# HolderDog_Simetric.net
KiCad netlist of a schematic drawn in Altium Designer
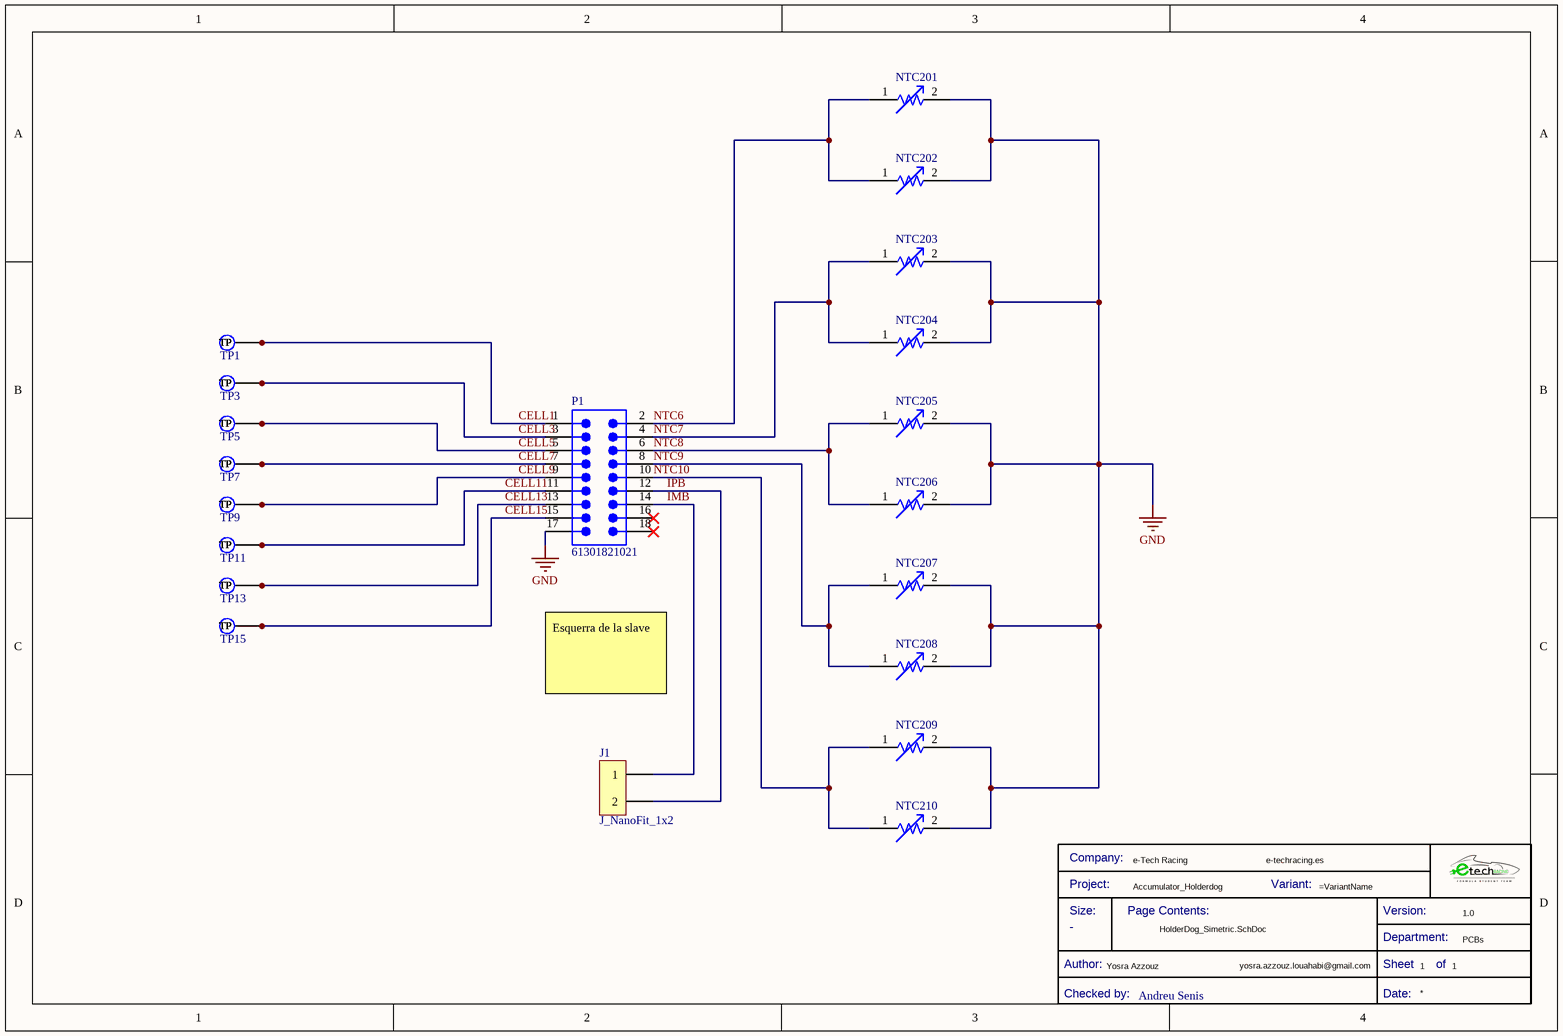
[diagram p0: HolderDog_Simetric.SchDoc]

(export (version "E")
  (design (tool "Eeschema 10.0.6"))
  (components
    (comp (ref "*")
      (value "Title Block_template")
      (description "Standard Title Block")
      (fields
        (field (name "SIZE") "-")
        (field (name ".CREATOR") "GP")
        (field (name ".PCBCHECK") "GP")
        (field (name ".SCHCHECK") "GP")
      )
      (libsource (lib "e-Tech_Racing") (part "Title Block_template"))
    )
    (comp (ref "J1")
      (value "J_NanoFit_1x2")
      (footprint "FP-105309-1102-MFG")
      (description "Conn HDR 2 POS 2.5mm Solder ST Thru-Hole 2 Terminal 1 Port Nano-Fit Tray")
      (libsource (lib "EMEA- E-Tech Racing- I'Escola d'Enginyeria de Barcelona Est") (part "Molex Nano-Fit"))
    )
    (comp (ref "NTC201")
      (value "NTC SMD 0805")
      (footprint "RESC2012X10N")
      (description "NTC 0805 package 10kR")
      (libsource (lib "EMEA- E-Tech Racing- I'Escola d'Enginyeria de Barcelona Est") (part "0805"))
    )
    (comp (ref "NTC202")
      (value "NTC SMD 0805")
      (footprint "RESC2012X10N")
      (description "NTC 0805 package 10kR")
      (libsource (lib "EMEA- E-Tech Racing- I'Escola d'Enginyeria de Barcelona Est") (part "0805"))
    )
    (comp (ref "NTC203")
      (value "NTC SMD 0805")
      (footprint "RESC2012X10N")
      (description "NTC 0805 package 10kR")
      (libsource (lib "EMEA- E-Tech Racing- I'Escola d'Enginyeria de Barcelona Est") (part "0805"))
    )
    (comp (ref "NTC204")
      (value "NTC SMD 0805")
      (footprint "RESC2012X10N")
      (description "NTC 0805 package 10kR")
      (libsource (lib "EMEA- E-Tech Racing- I'Escola d'Enginyeria de Barcelona Est") (part "0805"))
    )
    (comp (ref "NTC205")
      (value "NTC SMD 0805")
      (footprint "RESC2012X10N")
      (description "NTC 0805 package 10kR")
      (libsource (lib "EMEA- E-Tech Racing- I'Escola d'Enginyeria de Barcelona Est") (part "0805"))
    )
    (comp (ref "NTC206")
      (value "NTC SMD 0805")
      (footprint "RESC2012X10N")
      (description "NTC 0805 package 10kR")
      (libsource (lib "EMEA- E-Tech Racing- I'Escola d'Enginyeria de Barcelona Est") (part "0805"))
    )
    (comp (ref "NTC207")
      (value "NTC SMD 0805")
      (footprint "RESC2012X10N")
      (description "NTC 0805 package 10kR")
      (libsource (lib "EMEA- E-Tech Racing- I'Escola d'Enginyeria de Barcelona Est") (part "0805"))
    )
    (comp (ref "NTC208")
      (value "NTC SMD 0805")
      (footprint "RESC2012X10N")
      (description "NTC 0805 package 10kR")
      (libsource (lib "EMEA- E-Tech Racing- I'Escola d'Enginyeria de Barcelona Est") (part "0805"))
    )
    (comp (ref "NTC209")
      (value "NTC SMD 0805")
      (footprint "RESC2012X10N")
      (description "NTC 0805 package 10kR")
      (libsource (lib "EMEA- E-Tech Racing- I'Escola d'Enginyeria de Barcelona Est") (part "0805"))
    )
    (comp (ref "NTC210")
      (value "NTC SMD 0805")
      (footprint "RESC2012X10N")
      (description "NTC 0805 package 10kR")
      (libsource (lib "EMEA- E-Tech Racing- I'Escola d'Enginyeria de Barcelona Est") (part "0805"))
    )
    (comp (ref "P1")
      (value "61301821021")
      (footprint "61301821021")
      (libsource (lib "EMEA- E-Tech Racing- I'Escola d'Enginyeria de Barcelona Est") (part "Header_Male_2R_18P"))
    )
    (comp (ref "TP1")
      (value "Test Point")
      (footprint "TESTPOINT_WIDE")
      (description "TestPoint 5x5mm")
      (libsource (lib "e-Tech_Racing") (part "TestPoint_Wide"))
    )
    (comp (ref "TP3")
      (value "Test Point")
      (footprint "TESTPOINT_WIDE")
      (description "TestPoint 5x5mm")
      (libsource (lib "e-Tech_Racing") (part "TestPoint_Wide"))
    )
    (comp (ref "TP5")
      (value "Test Point")
      (footprint "TESTPOINT_WIDE")
      (description "TestPoint 5x5mm")
      (libsource (lib "e-Tech_Racing") (part "TestPoint_Wide"))
    )
    (comp (ref "TP7")
      (value "Test Point")
      (footprint "TESTPOINT_WIDE")
      (description "TestPoint 5x5mm")
      (libsource (lib "e-Tech_Racing") (part "TestPoint_Wide"))
    )
    (comp (ref "TP9")
      (value "Test Point")
      (footprint "TESTPOINT_WIDE")
      (description "TestPoint 5x5mm")
      (libsource (lib "e-Tech_Racing") (part "TestPoint_Wide"))
    )
    (comp (ref "TP11")
      (value "Test Point")
      (footprint "TESTPOINT_WIDE")
      (description "TestPoint 5x5mm")
      (libsource (lib "e-Tech_Racing") (part "TestPoint_Wide"))
    )
    (comp (ref "TP13")
      (value "Test Point")
      (footprint "TESTPOINT_WIDE")
      (description "TestPoint 5x5mm")
      (libsource (lib "e-Tech_Racing") (part "TestPoint_Wide"))
    )
    (comp (ref "TP15")
      (value "Test Point")
      (footprint "TESTPOINT_WIDE")
      (description "TestPoint 5x5mm")
      (libsource (lib "e-Tech_Racing") (part "TestPoint_Wide"))
    )
  )
  (nets
    (net (code "1") (name "/CELL1") (class "Default")
      (node (ref "P1") (pin "1") (pinfunction "1_1") (pintype "passive"))
      (node (ref "TP1") (pin "1") (pinfunction "TP_1") (pintype "passive"))
    )
    (net (code "2") (name "/CELL3") (class "Default")
      (node (ref "P1") (pin "3") (pinfunction "3_3") (pintype "passive"))
      (node (ref "TP3") (pin "1") (pinfunction "TP_1") (pintype "passive"))
    )
    (net (code "3") (name "/CELL5") (class "Default")
      (node (ref "P1") (pin "5") (pinfunction "5_5") (pintype "passive"))
      (node (ref "TP5") (pin "1") (pinfunction "TP_1") (pintype "passive"))
    )
    (net (code "4") (name "/CELL7") (class "Default")
      (node (ref "P1") (pin "7") (pinfunction "7_7") (pintype "passive"))
      (node (ref "TP7") (pin "1") (pinfunction "TP_1") (pintype "passive"))
    )
    (net (code "5") (name "/CELL9") (class "Default")
      (node (ref "P1") (pin "9") (pinfunction "9_9") (pintype "passive"))
      (node (ref "TP9") (pin "1") (pinfunction "TP_1") (pintype "passive"))
    )
    (net (code "6") (name "/CELL11") (class "Default")
      (node (ref "P1") (pin "11") (pinfunction "11_11") (pintype "passive"))
      (node (ref "TP11") (pin "1") (pinfunction "TP_1") (pintype "passive"))
    )
    (net (code "7") (name "/CELL13") (class "Default")
      (node (ref "P1") (pin "13") (pinfunction "13_13") (pintype "passive"))
      (node (ref "TP13") (pin "1") (pinfunction "TP_1") (pintype "passive"))
    )
    (net (code "8") (name "/CELL15") (class "Default")
      (node (ref "P1") (pin "15") (pinfunction "15_15") (pintype "passive"))
      (node (ref "TP15") (pin "1") (pinfunction "TP_1") (pintype "passive"))
    )
    (net (code "9") (name "/IMB") (class "Default")
      (node (ref "J1") (pin "1") (pinfunction "1_1") (pintype "passive"))
      (node (ref "P1") (pin "14") (pinfunction "14_14") (pintype "passive"))
    )
    (net (code "10") (name "/IPB") (class "Default")
      (node (ref "J1") (pin "2") (pinfunction "2_2") (pintype "passive"))
      (node (ref "P1") (pin "12") (pinfunction "12_12") (pintype "passive"))
    )
    (net (code "11") (name "/NTC6") (class "Default")
      (node (ref "NTC201") (pin "1") (pinfunction "1_1") (pintype "passive"))
      (node (ref "NTC202") (pin "1") (pinfunction "1_1") (pintype "passive"))
      (node (ref "P1") (pin "2") (pinfunction "2_2") (pintype "passive"))
    )
    (net (code "12") (name "/NTC7") (class "Default")
      (node (ref "NTC203") (pin "1") (pinfunction "1_1") (pintype "passive"))
      (node (ref "NTC204") (pin "1") (pinfunction "1_1") (pintype "passive"))
      (node (ref "P1") (pin "4") (pinfunction "4_4") (pintype "passive"))
    )
    (net (code "13") (name "/NTC8") (class "Default")
      (node (ref "NTC205") (pin "1") (pinfunction "1_1") (pintype "passive"))
      (node (ref "NTC206") (pin "1") (pinfunction "1_1") (pintype "passive"))
      (node (ref "P1") (pin "6") (pinfunction "6_6") (pintype "passive"))
    )
    (net (code "14") (name "/NTC9") (class "Default")
      (node (ref "NTC207") (pin "1") (pinfunction "1_1") (pintype "passive"))
      (node (ref "NTC208") (pin "1") (pinfunction "1_1") (pintype "passive"))
      (node (ref "P1") (pin "8") (pinfunction "8_8") (pintype "passive"))
    )
    (net (code "15") (name "/NTC10") (class "Default")
      (node (ref "NTC209") (pin "1") (pinfunction "1_1") (pintype "passive"))
      (node (ref "NTC210") (pin "1") (pinfunction "1_1") (pintype "passive"))
      (node (ref "P1") (pin "10") (pinfunction "10_10") (pintype "passive"))
    )
    (net (code "16") (name "GND") (class "Default")
      (node (ref "NTC201") (pin "2") (pinfunction "2_2") (pintype "passive"))
      (node (ref "NTC202") (pin "2") (pinfunction "2_2") (pintype "passive"))
      (node (ref "NTC203") (pin "2") (pinfunction "2_2") (pintype "passive"))
      (node (ref "NTC204") (pin "2") (pinfunction "2_2") (pintype "passive"))
      (node (ref "NTC205") (pin "2") (pinfunction "2_2") (pintype "passive"))
      (node (ref "NTC206") (pin "2") (pinfunction "2_2") (pintype "passive"))
      (node (ref "NTC207") (pin "2") (pinfunction "2_2") (pintype "passive"))
      (node (ref "NTC208") (pin "2") (pinfunction "2_2") (pintype "passive"))
      (node (ref "NTC209") (pin "2") (pinfunction "2_2") (pintype "passive"))
      (node (ref "NTC210") (pin "2") (pinfunction "2_2") (pintype "passive"))
      (node (ref "P1") (pin "17") (pinfunction "17_17") (pintype "passive"))
    )
    (net (code "17") (name "unconnected-(P1-Pad16)") (class "Default")
      (node (ref "P1") (pin "16") (pinfunction "16_16") (pintype "passive+no_connect"))
    )
    (net (code "18") (name "unconnected-(P1-Pad18)") (class "Default")
      (node (ref "P1") (pin "18") (pinfunction "18_18") (pintype "passive+no_connect"))
    )
  )
)
